# I2C_IR.net
KiCad netlist of a schematic drawn in EAGLE
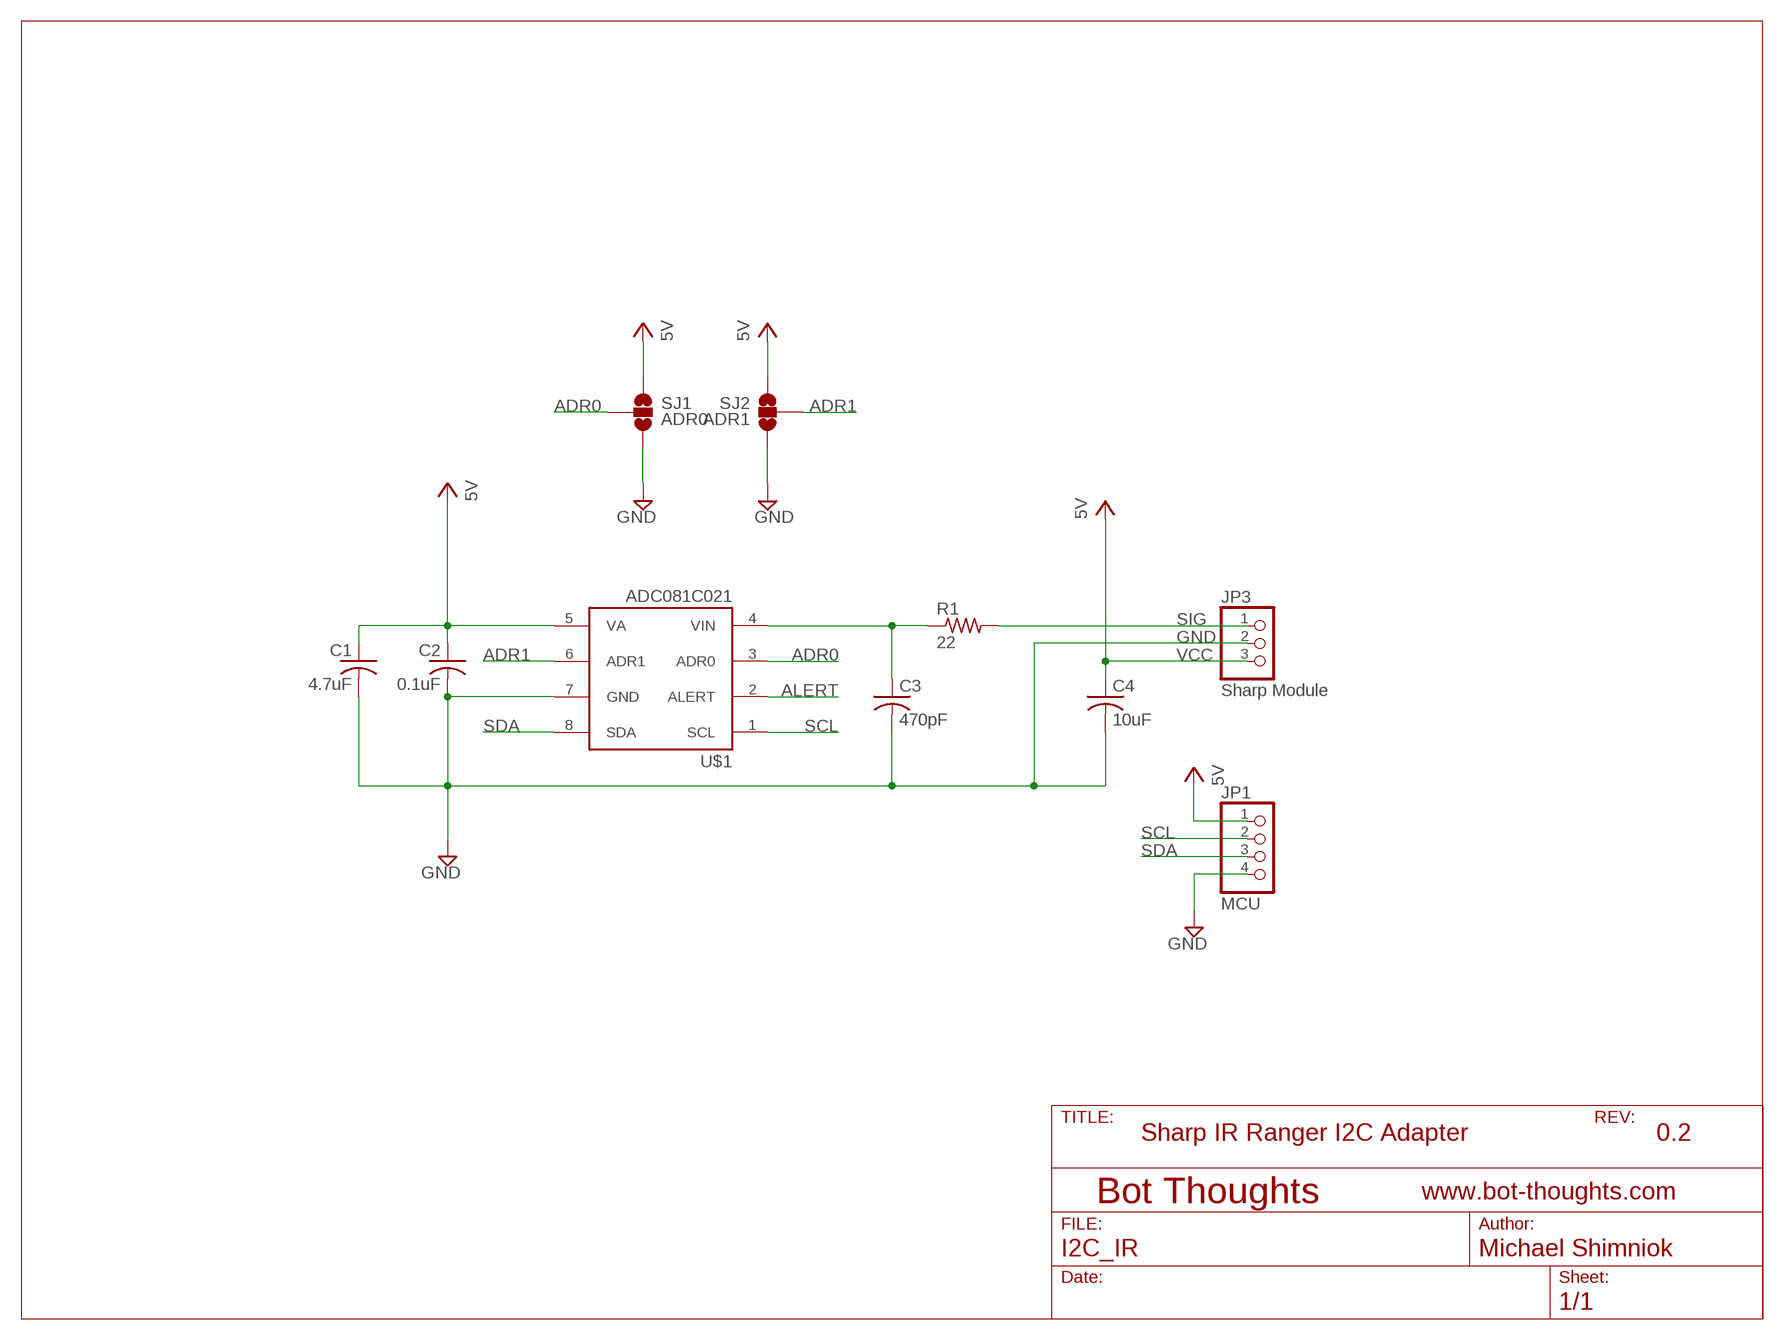
[diagram p0: schematic, sheet 1]

(export (version "E")
  (design (tool "Eeschema 10.0.6"))
  (components
    (comp (ref "C1")
      (value "4.7uF")
      (footprint "eagle-import:C0603")
      (libsource (lib "eagle-import") (part "C-USC0603"))
    )
    (comp (ref "C2")
      (value "0.1uF")
      (footprint "eagle-import:C0603")
      (libsource (lib "eagle-import") (part "C-USC0603"))
    )
    (comp (ref "C3")
      (value "470pF")
      (footprint "eagle-import:C0603")
      (libsource (lib "eagle-import") (part "C-USC0603"))
    )
    (comp (ref "C4")
      (value "10uF")
      (footprint "eagle-import:C0603")
      (libsource (lib "eagle-import") (part "C-USC0603"))
    )
    (comp (ref "JP1")
      (value "MCU")
      (footprint "eagle-import:1X04-S")
      (libsource (lib "eagle-import") (part "PINHD-1X04_2.54-S"))
    )
    (comp (ref "JP3")
      (value "Sharp Module")
      (footprint "eagle-import:1X03M")
      (libsource (lib "eagle-import") (part "PINHD-1X03_2.00"))
    )
    (comp (ref "R1")
      (value "22")
      (footprint "eagle-import:R0603")
      (libsource (lib "eagle-import") (part "R-US_R0603"))
    )
    (comp (ref "SJ1")
      (value "ADR0")
      (footprint "eagle-import:SJ_3")
      (libsource (lib "eagle-import") (part "SOLDERJUMPER_2WAYS"))
    )
    (comp (ref "SJ2")
      (value "ADR1")
      (footprint "eagle-import:SJ_3")
      (libsource (lib "eagle-import") (part "SOLDERJUMPER_2WAYS"))
    )
    (comp (ref "U$1")
      (value "ADC081C021")
      (footprint "eagle-import:MSOP8_0.65")
      (libsource (lib "eagle-import") (part "ADC081C021"))
    )
  )
  (nets
    (net (code "1") (name "/ADR0") (class "Default")
      (node (ref "SJ1") (pin "2") (pinfunction "2_2") (pintype "passive"))
      (node (ref "U$1") (pin "3") (pinfunction "ADR0_3") (pintype "bidirectional"))
    )
    (net (code "2") (name "/ADR1") (class "Default")
      (node (ref "SJ2") (pin "2") (pinfunction "2_2") (pintype "passive"))
      (node (ref "U$1") (pin "6") (pinfunction "ADR1_6") (pintype "bidirectional"))
    )
    (net (code "3") (name "/ALERT") (class "Default")
      (node (ref "U$1") (pin "2") (pinfunction "ALERT_2") (pintype "bidirectional"))
    )
    (net (code "4") (name "/SCL") (class "Default")
      (node (ref "JP1") (pin "2") (pinfunction "2_2") (pintype "passive"))
      (node (ref "U$1") (pin "1") (pinfunction "SCL_1") (pintype "bidirectional"))
    )
    (net (code "5") (name "/SDA") (class "Default")
      (node (ref "JP1") (pin "3") (pinfunction "3_3") (pintype "passive"))
      (node (ref "U$1") (pin "8") (pinfunction "SDA_8") (pintype "bidirectional"))
    )
    (net (code "6") (name "/SIG") (class "Default")
      (node (ref "JP3") (pin "1") (pinfunction "1_1") (pintype "passive"))
      (node (ref "R1") (pin "2") (pinfunction "2_2") (pintype "passive"))
    )
    (net (code "7") (name "5V") (class "Default")
      (node (ref "C1") (pin "1") (pinfunction "1_1") (pintype "passive"))
      (node (ref "C2") (pin "1") (pinfunction "1_1") (pintype "passive"))
      (node (ref "C4") (pin "1") (pinfunction "1_1") (pintype "passive"))
      (node (ref "JP1") (pin "1") (pinfunction "1_1") (pintype "passive"))
      (node (ref "JP3") (pin "3") (pinfunction "3_3") (pintype "passive"))
      (node (ref "SJ1") (pin "1") (pinfunction "1_1") (pintype "passive"))
      (node (ref "SJ2") (pin "1") (pinfunction "1_1") (pintype "passive"))
      (node (ref "U$1") (pin "5") (pinfunction "VA_5") (pintype "bidirectional"))
    )
    (net (code "8") (name "GND") (class "Default")
      (node (ref "C1") (pin "2") (pinfunction "2_2") (pintype "passive"))
      (node (ref "C2") (pin "2") (pinfunction "2_2") (pintype "passive"))
      (node (ref "C3") (pin "2") (pinfunction "2_2") (pintype "passive"))
      (node (ref "C4") (pin "2") (pinfunction "2_2") (pintype "passive"))
      (node (ref "JP1") (pin "4") (pinfunction "4_4") (pintype "passive"))
      (node (ref "JP3") (pin "2") (pinfunction "2_2") (pintype "passive"))
      (node (ref "SJ1") (pin "3") (pinfunction "3_3") (pintype "passive"))
      (node (ref "SJ2") (pin "3") (pinfunction "3_3") (pintype "passive"))
      (node (ref "U$1") (pin "7") (pinfunction "GND_7") (pintype "bidirectional"))
    )
    (net (code "9") (name "Net-(U$1-VIN)") (class "Default")
      (node (ref "C3") (pin "1") (pinfunction "1_1") (pintype "passive"))
      (node (ref "R1") (pin "1") (pinfunction "1_1") (pintype "passive"))
      (node (ref "U$1") (pin "4") (pinfunction "VIN_4") (pintype "bidirectional"))
    )
  )
)
